# SCH_08_Output.net
KiCad netlist of a schematic drawn in Altium Designer
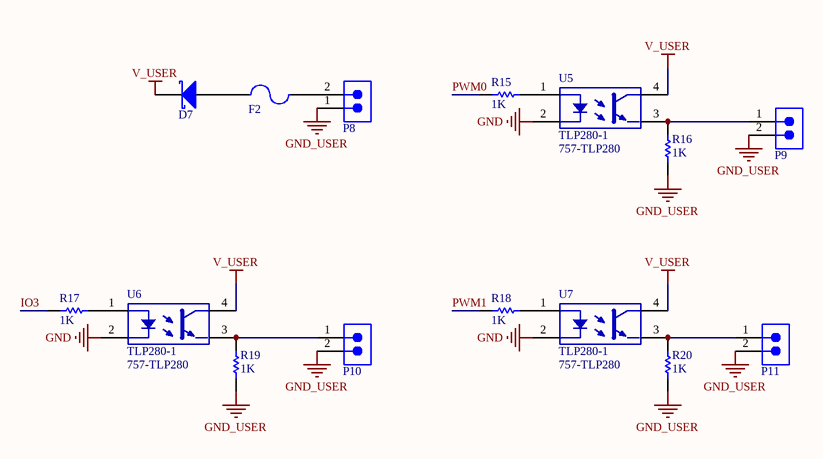
[diagram p0: SCH_08_Output.SchDoc]

(export (version "E")
  (design (tool "Eeschema 10.0.6"))
  (components
    (comp (ref "D7")
      (value "D Schottky")
      (footprint "SS34")
      (description "Schottky Diode")
      (fields (field (name "PUBLISHER") "Altium Limited"))
      (libsource (lib "PIF_Library") (part "D Schottky"))
    )
    (comp (ref "F2") (value "Fuse") (footprint "FUSE SMD") (libsource (lib "PIF_Library") (part "Fuse")))
    (comp (ref "P8")
      (value "691312510002")
      (footprint "691312510002")
      (description "WR-TBL Series 312 Open Horizontal PCB Header, THT, pitch 5.08mm, 2p")
      (fields (field (name "MANUFACTURER") "Wurth Elektronik"))
      (libsource (lib "Altium_WR-TBL (rev22b)") (part "691312510002"))
    )
    (comp (ref "P9")
      (value "691312510002")
      (footprint "691312510002")
      (description "WR-TBL Series 312 Open Horizontal PCB Header, THT, pitch 5.08mm, 2p")
      (fields (field (name "MANUFACTURER") "Wurth Elektronik"))
      (libsource (lib "Altium_WR-TBL (rev22b)") (part "691312510002"))
    )
    (comp (ref "P10")
      (value "691312510002")
      (footprint "691312510002")
      (description "WR-TBL Series 312 Open Horizontal PCB Header, THT, pitch 5.08mm, 2p")
      (fields (field (name "MANUFACTURER") "Wurth Elektronik"))
      (libsource (lib "Altium_WR-TBL (rev22b)") (part "691312510002"))
    )
    (comp (ref "P11")
      (value "691312510002")
      (footprint "691312510002")
      (description "WR-TBL Series 312 Open Horizontal PCB Header, THT, pitch 5.08mm, 2p")
      (fields (field (name "MANUFACTURER") "Wurth Elektronik"))
      (libsource (lib "Altium_WR-TBL (rev22b)") (part "691312510002"))
    )
    (comp (ref "R15")
      (value "1K")
      (footprint "RES-SM-0603")
      (description "Resistor")
      (fields (field (name "Comment") "RESISTOR SMD"))
      (libsource (lib "PIF_Library") (part "RESISTOR SMD"))
    )
    (comp (ref "R16")
      (value "1K")
      (footprint "RES-SM-0603")
      (description "Resistor")
      (fields (field (name "Comment") "RESISTOR SMD"))
      (libsource (lib "PIF_Library") (part "RESISTOR SMD"))
    )
    (comp (ref "R17")
      (value "1K")
      (footprint "RES-SM-0603")
      (description "Resistor")
      (fields (field (name "Comment") "RESISTOR SMD"))
      (libsource (lib "PIF_Library") (part "RESISTOR SMD"))
    )
    (comp (ref "R18")
      (value "1K")
      (footprint "RES-SM-0603")
      (description "Resistor")
      (fields (field (name "Comment") "RESISTOR SMD"))
      (libsource (lib "PIF_Library") (part "RESISTOR SMD"))
    )
    (comp (ref "R19")
      (value "1K")
      (footprint "RES-SM-0603")
      (description "Resistor")
      (fields (field (name "Comment") "RESISTOR SMD"))
      (libsource (lib "PIF_Library") (part "RESISTOR SMD"))
    )
    (comp (ref "R20")
      (value "1K")
      (footprint "RES-SM-0603")
      (description "Resistor")
      (fields (field (name "Comment") "RESISTOR SMD"))
      (libsource (lib "PIF_Library") (part "RESISTOR SMD"))
    )
    (comp (ref "U5")
      (value "TLP280-1")
      (footprint "SOIC127P700X240-4N")
      (description "Transistor Output Optocouplers 80Vceo 2500Vrms AC input")
      (fields (field (name "SUPPLIER PART NUMBER 1") "757-TLP280"))
      (libsource (lib "Huy_Lib") (part "TLP280-1"))
    )
    (comp (ref "U6")
      (value "TLP280-1")
      (footprint "SOIC127P700X240-4N")
      (description "Transistor Output Optocouplers 80Vceo 2500Vrms AC input")
      (fields (field (name "SUPPLIER PART NUMBER 1") "757-TLP280"))
      (libsource (lib "Huy_Lib") (part "TLP280-1"))
    )
    (comp (ref "U7")
      (value "TLP280-1")
      (footprint "SOIC127P700X240-4N")
      (description "Transistor Output Optocouplers 80Vceo 2500Vrms AC input")
      (fields (field (name "SUPPLIER PART NUMBER 1") "757-TLP280"))
      (libsource (lib "Huy_Lib") (part "TLP280-1"))
    )
  )
  (nets
    (net (code "1") (name "/IO3") (class "Default")
      (node (ref "R17") (pin "2") (pinfunction "2_2") (pintype "passive"))
    )
    (net (code "2") (name "/PWM0") (class "Default")
      (node (ref "R15") (pin "2") (pinfunction "2_2") (pintype "passive"))
    )
    (net (code "3") (name "/PWM1") (class "Default")
      (node (ref "R18") (pin "2") (pinfunction "2_2") (pintype "passive"))
    )
    (net (code "4") (name "GND") (class "Default")
      (node (ref "U5") (pin "2") (pinfunction "2_2") (pintype "passive"))
      (node (ref "U6") (pin "2") (pinfunction "2_2") (pintype "passive"))
      (node (ref "U7") (pin "2") (pinfunction "2_2") (pintype "passive"))
    )
    (net (code "5") (name "GND_USER") (class "Default")
      (node (ref "P10") (pin "2") (pinfunction "2_2") (pintype "passive"))
      (node (ref "P11") (pin "2") (pinfunction "2_2") (pintype "passive"))
      (node (ref "P8") (pin "1") (pinfunction "1_1") (pintype "passive"))
      (node (ref "P9") (pin "2") (pinfunction "2_2") (pintype "passive"))
      (node (ref "R16") (pin "1") (pinfunction "1_1") (pintype "passive"))
      (node (ref "R19") (pin "1") (pinfunction "1_1") (pintype "passive"))
      (node (ref "R20") (pin "1") (pinfunction "1_1") (pintype "passive"))
    )
    (net (code "6") (name "Net-(D7-A)") (class "Default")
      (node (ref "D7") (pin "1") (pinfunction "A_1") (pintype "passive"))
      (node (ref "F2") (pin "1") (pinfunction "1_1") (pintype "passive"))
    )
    (net (code "7") (name "Net-(F2-Pad2)") (class "Default")
      (node (ref "F2") (pin "2") (pinfunction "2_2") (pintype "passive"))
      (node (ref "P8") (pin "2") (pinfunction "2_2") (pintype "passive"))
    )
    (net (code "8") (name "Net-(P9-Pad1)") (class "Default")
      (node (ref "P9") (pin "1") (pinfunction "1_1") (pintype "passive"))
      (node (ref "R16") (pin "2") (pinfunction "2_2") (pintype "passive"))
      (node (ref "U5") (pin "3") (pinfunction "3_3") (pintype "passive"))
    )
    (net (code "9") (name "Net-(P10-Pad1)") (class "Default")
      (node (ref "P10") (pin "1") (pinfunction "1_1") (pintype "passive"))
      (node (ref "R19") (pin "2") (pinfunction "2_2") (pintype "passive"))
      (node (ref "U6") (pin "3") (pinfunction "3_3") (pintype "passive"))
    )
    (net (code "10") (name "Net-(P11-Pad1)") (class "Default")
      (node (ref "P11") (pin "1") (pinfunction "1_1") (pintype "passive"))
      (node (ref "R20") (pin "2") (pinfunction "2_2") (pintype "passive"))
      (node (ref "U7") (pin "3") (pinfunction "3_3") (pintype "passive"))
    )
    (net (code "11") (name "Net-(R15-Pad1)") (class "Default")
      (node (ref "R15") (pin "1") (pinfunction "1_1") (pintype "passive"))
      (node (ref "U5") (pin "1") (pinfunction "1_1") (pintype "passive"))
    )
    (net (code "12") (name "Net-(R17-Pad1)") (class "Default")
      (node (ref "R17") (pin "1") (pinfunction "1_1") (pintype "passive"))
      (node (ref "U6") (pin "1") (pinfunction "1_1") (pintype "passive"))
    )
    (net (code "13") (name "Net-(R18-Pad1)") (class "Default")
      (node (ref "R18") (pin "1") (pinfunction "1_1") (pintype "passive"))
      (node (ref "U7") (pin "1") (pinfunction "1_1") (pintype "passive"))
    )
    (net (code "14") (name "V_USER") (class "Default")
      (node (ref "D7") (pin "2") (pinfunction "K_2") (pintype "passive"))
      (node (ref "U5") (pin "4") (pinfunction "4_4") (pintype "passive"))
      (node (ref "U6") (pin "4") (pinfunction "4_4") (pintype "passive"))
      (node (ref "U7") (pin "4") (pinfunction "4_4") (pintype "passive"))
    )
  )
)
